# CCM_0003.net
KiCad netlist of a schematic drawn in EAGLE
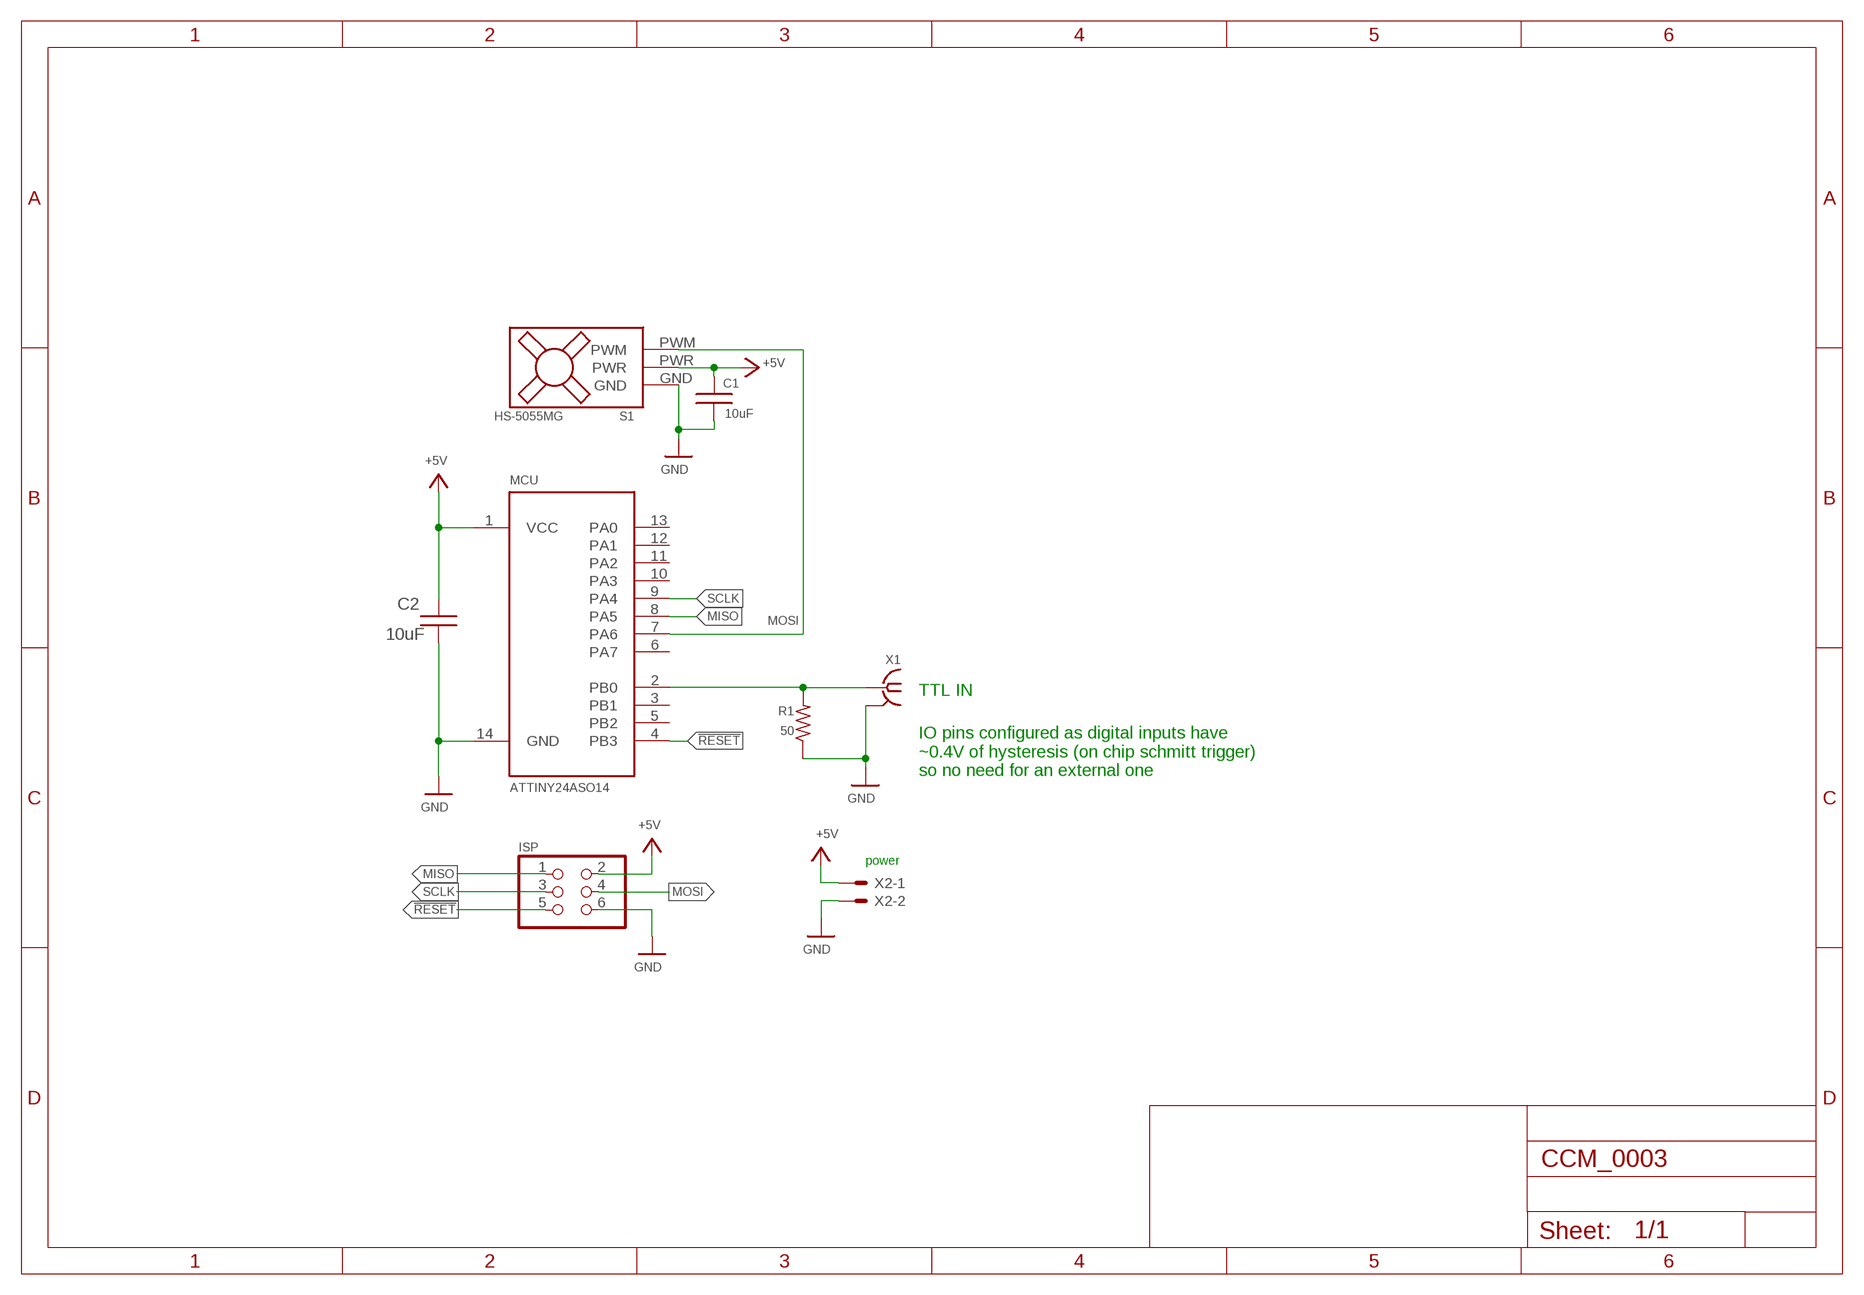
[diagram p0: schematic, sheet 1]

(export (version "E")
  (design (tool "Eeschema 10.0.6"))
  (components
    (comp (ref "C1")
      (value "10uF")
      (footprint "eagle-import:0603")
      (libsource (lib "eagle-import") (part "CAPACITOR0603"))
    )
    (comp (ref "C2")
      (value "10uF")
      (footprint "eagle-import:0603")
      (libsource (lib "eagle-import") (part "CAPACITOR0603"))
    )
    (comp (ref "ISP")
      (value "ISP")
      (footprint "eagle-import:2X03")
      (libsource (lib "eagle-import") (part "PINHD-2X3"))
    )
    (comp (ref "MCU")
      (value "ATTINY24ASO14")
      (footprint "eagle-import:SO14")
      (libsource (lib "eagle-import") (part "ATTINY24ASO14"))
    )
    (comp (ref "R1")
      (value "50")
      (footprint "eagle-import:R2010")
      (libsource (lib "eagle-import") (part "R-US_R2010"))
    )
    (comp (ref "S1")
      (value "HS-5055MG")
      (footprint "eagle-import:HS-5055MG")
      (libsource (lib "eagle-import") (part "HS-5055MG"))
    )
    (comp (ref "X1")
      (value "BU-SMA-H")
      (footprint "eagle-import:BU-SMA-H")
      (libsource (lib "eagle-import") (part "BU-SMA-H"))
    )
    (comp (ref "X2")
      (value "22-23-2021")
      (footprint "eagle-import:22-23-2021")
      (fields (field (name "MF") "MOLEX"))
      (libsource (lib "eagle-import") (part "22-23-2021"))
    )
  )
  (nets
    (net (code "1") (name "+5V") (class "Default")
      (node (ref "C1") (pin "1") (pinfunction "1_1") (pintype "passive"))
      (node (ref "C2") (pin "1") (pinfunction "1_1") (pintype "passive"))
      (node (ref "ISP") (pin "2") (pinfunction "2_2") (pintype "passive"))
      (node (ref "MCU") (pin "1") (pinfunction "VCC_1") (pintype "bidirectional"))
      (node (ref "S1") (pin "PWR") (pinfunction "PWR_PWR") (pintype "bidirectional"))
      (node (ref "X2") (pin "1") (pinfunction "S_1") (pintype "passive"))
    )
    (net (code "2") (name "/~{RESET}") (class "Default")
      (node (ref "ISP") (pin "5") (pinfunction "5_5") (pintype "passive"))
      (node (ref "MCU") (pin "4") (pinfunction "PB3_4") (pintype "bidirectional"))
    )
    (net (code "3") (name "GND") (class "Default")
      (node (ref "C1") (pin "2") (pinfunction "2_2") (pintype "passive"))
      (node (ref "C2") (pin "2") (pinfunction "2_2") (pintype "passive"))
      (node (ref "ISP") (pin "6") (pinfunction "6_6") (pintype "passive"))
      (node (ref "MCU") (pin "14") (pinfunction "GND_14") (pintype "bidirectional"))
      (node (ref "R1") (pin "1") (pinfunction "1_1") (pintype "passive"))
      (node (ref "S1") (pin "GND") (pinfunction "GND_GND") (pintype "bidirectional"))
      (node (ref "X1") (pin "2") (pinfunction "2_2") (pintype "passive"))
      (node (ref "X1") (pin "3") (pinfunction "2_3") (pintype "passive"))
      (node (ref "X1") (pin "4") (pinfunction "2_4") (pintype "passive"))
      (node (ref "X1") (pin "5") (pinfunction "2_5") (pintype "passive"))
      (node (ref "X2") (pin "2") (pinfunction "S_2") (pintype "passive"))
    )
    (net (code "4") (name "MISO") (class "Default")
      (node (ref "ISP") (pin "1") (pinfunction "1_1") (pintype "passive"))
      (node (ref "MCU") (pin "8") (pinfunction "PA5_8") (pintype "bidirectional"))
    )
    (net (code "5") (name "MOSI") (class "Default")
      (node (ref "ISP") (pin "4") (pinfunction "4_4") (pintype "passive"))
      (node (ref "MCU") (pin "7") (pinfunction "PA6_7") (pintype "bidirectional"))
      (node (ref "S1") (pin "PWM") (pinfunction "PWM_PWM") (pintype "bidirectional"))
    )
    (net (code "6") (name "Net-(MCU-PB0)") (class "Default")
      (node (ref "MCU") (pin "2") (pinfunction "PB0_2") (pintype "bidirectional"))
      (node (ref "R1") (pin "2") (pinfunction "2_2") (pintype "passive"))
      (node (ref "X1") (pin "1") (pinfunction "1_1") (pintype "passive"))
    )
    (net (code "7") (name "SCLK") (class "Default")
      (node (ref "ISP") (pin "3") (pinfunction "3_3") (pintype "passive"))
      (node (ref "MCU") (pin "9") (pinfunction "PA4_9") (pintype "bidirectional"))
    )
    (net (code "8") (name "unconnected-(MCU-PA0-Pad13)") (class "Default")
      (node (ref "MCU") (pin "13") (pinfunction "PA0_13") (pintype "bidirectional"))
    )
    (net (code "9") (name "unconnected-(MCU-PA1-Pad12)") (class "Default")
      (node (ref "MCU") (pin "12") (pinfunction "PA1_12") (pintype "bidirectional"))
    )
    (net (code "10") (name "unconnected-(MCU-PA2-Pad11)") (class "Default")
      (node (ref "MCU") (pin "11") (pinfunction "PA2_11") (pintype "bidirectional"))
    )
    (net (code "11") (name "unconnected-(MCU-PA3-Pad10)") (class "Default")
      (node (ref "MCU") (pin "10") (pinfunction "PA3_10") (pintype "bidirectional"))
    )
    (net (code "12") (name "unconnected-(MCU-PA7-Pad6)") (class "Default")
      (node (ref "MCU") (pin "6") (pinfunction "PA7_6") (pintype "bidirectional"))
    )
    (net (code "13") (name "unconnected-(MCU-PB1-Pad3)") (class "Default")
      (node (ref "MCU") (pin "3") (pinfunction "PB1_3") (pintype "bidirectional"))
    )
    (net (code "14") (name "unconnected-(MCU-PB2-Pad5)") (class "Default")
      (node (ref "MCU") (pin "5") (pinfunction "PB2_5") (pintype "bidirectional"))
    )
  )
)
